# Bike.net
KiCad netlist of a schematic drawn in EAGLE
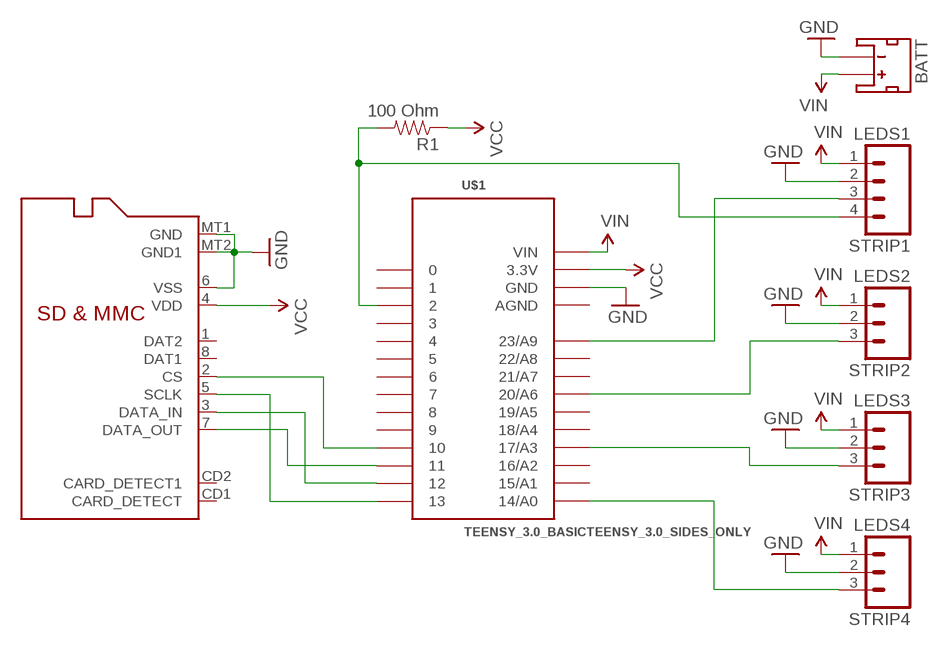
[diagram p0: schematic, sheet 1]

(export (version "E")
  (design (tool "Eeschema 10.0.6"))
  (components
    (comp (ref "BATT")
      (value "3.7V")
      (footprint "eagle-import:JST-2-SMD")
      (libsource (lib "eagle-import") (part "JST_2MM_MALE"))
    )
    (comp (ref "R1")
      (value "100 Ohm")
      (footprint "eagle-import:AXIAL-0.3EZ")
      (libsource (lib "eagle-import") (part "RESISTOREZ"))
    )
    (comp (ref "SD")
      (value "MICROSD")
      (footprint "eagle-import:MICROSD")
      (libsource (lib "eagle-import") (part "MICROSD"))
    )
    (comp (ref "STRIP1")
      (value "LEDS1")
      (footprint "eagle-import:JST-4-PTH")
      (libsource (lib "eagle-import") (part "M04JST-PTH"))
    )
    (comp (ref "STRIP2")
      (value "LEDS2")
      (footprint "eagle-import:JST-3-PTH")
      (libsource (lib "eagle-import") (part "M03JST-PTH"))
    )
    (comp (ref "STRIP3")
      (value "LEDS3")
      (footprint "eagle-import:JST-3-PTH")
      (libsource (lib "eagle-import") (part "M03JST-PTH"))
    )
    (comp (ref "STRIP4")
      (value "LEDS4")
      (footprint "eagle-import:JST-3-PTH")
      (libsource (lib "eagle-import") (part "M03JST-PTH"))
    )
    (comp (ref "U$1")
      (value "TEENSY_3.0_BASICTEENSY_3.0_SIDES_ONLY")
      (footprint "eagle-import:TEENSY_3.0_BASIC")
      (libsource (lib "eagle-import") (part "TEENSY_3.0_BASICTEENSY_3.0_SIDES_ONLY"))
    )
  )
  (nets
    (net (code "1") (name "/AGND") (class "Default")
      (node (ref "U$1") (pin "AGND") (pinfunction "AGND_AGND") (pintype "power_in"))
    )
    (net (code "2") (name "GND") (class "Default")
      (node (ref "BATT") (pin "1") (pinfunction "-_1") (pintype "bidirectional"))
      (node (ref "SD") (pin "6") (pinfunction "VSS_6") (pintype "power_in"))
      (node (ref "SD") (pin "MT1") (pinfunction "GND_MT1") (pintype "power_in"))
      (node (ref "SD") (pin "MT2") (pinfunction "GND1_MT2") (pintype "power_in"))
      (node (ref "STRIP1") (pin "2") (pinfunction "2_2") (pintype "passive"))
      (node (ref "STRIP2") (pin "2") (pinfunction "2_2") (pintype "passive"))
      (node (ref "STRIP3") (pin "2") (pinfunction "2_2") (pintype "passive"))
      (node (ref "STRIP4") (pin "2") (pinfunction "2_2") (pintype "passive"))
      (node (ref "U$1") (pin "GND") (pinfunction "GND_GND") (pintype "power_in"))
    )
    (net (code "3") (name "Net-(R1-2)") (class "Default")
      (node (ref "R1") (pin "P$2") (pinfunction "2_P$2") (pintype "passive"))
      (node (ref "STRIP1") (pin "4") (pinfunction "4_4") (pintype "passive"))
      (node (ref "U$1") (pin "2") (pinfunction "2_2") (pintype "bidirectional"))
    )
    (net (code "4") (name "Net-(SD-CS)") (class "Default")
      (node (ref "SD") (pin "2") (pinfunction "CS_2") (pintype "input"))
      (node (ref "U$1") (pin "10") (pinfunction "10_10") (pintype "bidirectional"))
    )
    (net (code "5") (name "Net-(SD-DATA_IN)") (class "Default")
      (node (ref "SD") (pin "3") (pinfunction "DATA_IN_3") (pintype "input"))
      (node (ref "U$1") (pin "12") (pinfunction "12_12") (pintype "bidirectional"))
    )
    (net (code "6") (name "Net-(SD-DATA_OUT)") (class "Default")
      (node (ref "SD") (pin "7") (pinfunction "DATA_OUT_7") (pintype "output"))
      (node (ref "U$1") (pin "11") (pinfunction "11_11") (pintype "bidirectional"))
    )
    (net (code "7") (name "Net-(SD-SCLK)") (class "Default")
      (node (ref "SD") (pin "5") (pinfunction "SCLK_5") (pintype "input"))
      (node (ref "U$1") (pin "13") (pinfunction "13_13") (pintype "bidirectional"))
    )
    (net (code "8") (name "Net-(STRIP1-Pad3)") (class "Default")
      (node (ref "STRIP1") (pin "3") (pinfunction "3_3") (pintype "passive"))
      (node (ref "U$1") (pin "23/A9") (pinfunction "23/A9_23/A9") (pintype "bidirectional"))
    )
    (net (code "9") (name "Net-(STRIP2-Pad3)") (class "Default")
      (node (ref "STRIP2") (pin "3") (pinfunction "3_3") (pintype "passive"))
      (node (ref "U$1") (pin "20/A6") (pinfunction "20/A6_20/A6") (pintype "bidirectional"))
    )
    (net (code "10") (name "Net-(STRIP3-Pad3)") (class "Default")
      (node (ref "STRIP3") (pin "3") (pinfunction "3_3") (pintype "passive"))
      (node (ref "U$1") (pin "17/A3") (pinfunction "17/A3_17/A3") (pintype "bidirectional"))
    )
    (net (code "11") (name "Net-(STRIP4-Pad3)") (class "Default")
      (node (ref "STRIP4") (pin "3") (pinfunction "3_3") (pintype "passive"))
      (node (ref "U$1") (pin "14/A0") (pinfunction "14/A0_14/A0") (pintype "bidirectional"))
    )
    (net (code "12") (name "VCC") (class "Default")
      (node (ref "R1") (pin "P$1") (pinfunction "1_P$1") (pintype "passive"))
      (node (ref "SD") (pin "4") (pinfunction "VDD_4") (pintype "power_in"))
      (node (ref "U$1") (pin "3.3V") (pinfunction "3.3V_3.3V") (pintype "power_in"))
    )
    (net (code "13") (name "VIN") (class "Default")
      (node (ref "BATT") (pin "2") (pinfunction "+_2") (pintype "bidirectional"))
      (node (ref "STRIP1") (pin "1") (pinfunction "1_1") (pintype "passive"))
      (node (ref "STRIP2") (pin "1") (pinfunction "1_1") (pintype "passive"))
      (node (ref "STRIP3") (pin "1") (pinfunction "1_1") (pintype "passive"))
      (node (ref "STRIP4") (pin "1") (pinfunction "1_1") (pintype "passive"))
      (node (ref "U$1") (pin "VIN") (pinfunction "VIN_VIN") (pintype "power_in"))
    )
    (net (code "14") (name "unconnected-(BATT-PAD1-PadNC1)") (class "Default")
      (node (ref "BATT") (pin "NC1") (pinfunction "PAD1_NC1") (pintype "bidirectional"))
    )
    (net (code "15") (name "unconnected-(BATT-PAD2-PadNC2)") (class "Default")
      (node (ref "BATT") (pin "NC2") (pinfunction "PAD2_NC2") (pintype "bidirectional"))
    )
    (net (code "16") (name "unconnected-(SD-CARD_DETECT-PadCD1)") (class "Default")
      (node (ref "SD") (pin "CD1") (pinfunction "CARD_DETECT_CD1") (pintype "passive"))
    )
    (net (code "17") (name "unconnected-(SD-CARD_DETECT1-PadCD2)") (class "Default")
      (node (ref "SD") (pin "CD2") (pinfunction "CARD_DETECT1_CD2") (pintype "passive"))
    )
    (net (code "18") (name "unconnected-(SD-DAT1-Pad8)") (class "Default")
      (node (ref "SD") (pin "8") (pinfunction "DAT1_8") (pintype "bidirectional"))
    )
    (net (code "19") (name "unconnected-(SD-DAT2-Pad1)") (class "Default")
      (node (ref "SD") (pin "1") (pinfunction "DAT2_1") (pintype "bidirectional"))
    )
    (net (code "20") (name "unconnected-(U$1-Pad0)") (class "Default")
      (node (ref "U$1") (pin "0") (pinfunction "0_0") (pintype "bidirectional"))
    )
    (net (code "21") (name "unconnected-(U$1-Pad1)") (class "Default")
      (node (ref "U$1") (pin "1") (pinfunction "1_1") (pintype "bidirectional"))
    )
    (net (code "22") (name "unconnected-(U$1-Pad3)") (class "Default")
      (node (ref "U$1") (pin "3") (pinfunction "3_3") (pintype "bidirectional"))
    )
    (net (code "23") (name "unconnected-(U$1-Pad4)") (class "Default")
      (node (ref "U$1") (pin "4") (pinfunction "4_4") (pintype "bidirectional"))
    )
    (net (code "24") (name "unconnected-(U$1-Pad5)") (class "Default")
      (node (ref "U$1") (pin "5") (pinfunction "5_5") (pintype "bidirectional"))
    )
    (net (code "25") (name "unconnected-(U$1-Pad6)") (class "Default")
      (node (ref "U$1") (pin "6") (pinfunction "6_6") (pintype "bidirectional"))
    )
    (net (code "26") (name "unconnected-(U$1-Pad7)") (class "Default")
      (node (ref "U$1") (pin "7") (pinfunction "7_7") (pintype "bidirectional"))
    )
    (net (code "27") (name "unconnected-(U$1-Pad8)") (class "Default")
      (node (ref "U$1") (pin "8") (pinfunction "8_8") (pintype "bidirectional"))
    )
    (net (code "28") (name "unconnected-(U$1-Pad9)") (class "Default")
      (node (ref "U$1") (pin "9") (pinfunction "9_9") (pintype "bidirectional"))
    )
    (net (code "29") (name "unconnected-(U$1-Pad15{slash}A1)") (class "Default")
      (node (ref "U$1") (pin "15/A1") (pinfunction "15/A1_15/A1") (pintype "bidirectional"))
    )
    (net (code "30") (name "unconnected-(U$1-Pad16{slash}A2)") (class "Default")
      (node (ref "U$1") (pin "16/A2") (pinfunction "16/A2_16/A2") (pintype "bidirectional"))
    )
    (net (code "31") (name "unconnected-(U$1-Pad18{slash}A4)") (class "Default")
      (node (ref "U$1") (pin "18/A4") (pinfunction "18/A4_18/A4") (pintype "bidirectional"))
    )
    (net (code "32") (name "unconnected-(U$1-Pad19{slash}A5)") (class "Default")
      (node (ref "U$1") (pin "19/A5") (pinfunction "19/A5_19/A5") (pintype "bidirectional"))
    )
    (net (code "33") (name "unconnected-(U$1-Pad21{slash}A7)") (class "Default")
      (node (ref "U$1") (pin "21/A7") (pinfunction "21/A7_21/A7") (pintype "bidirectional"))
    )
    (net (code "34") (name "unconnected-(U$1-Pad22{slash}A8)") (class "Default")
      (node (ref "U$1") (pin "22/A8") (pinfunction "22/A8_22/A8") (pintype "bidirectional"))
    )
  )
)
